# Sheet1.net
KiCad netlist of a schematic drawn in Altium Designer
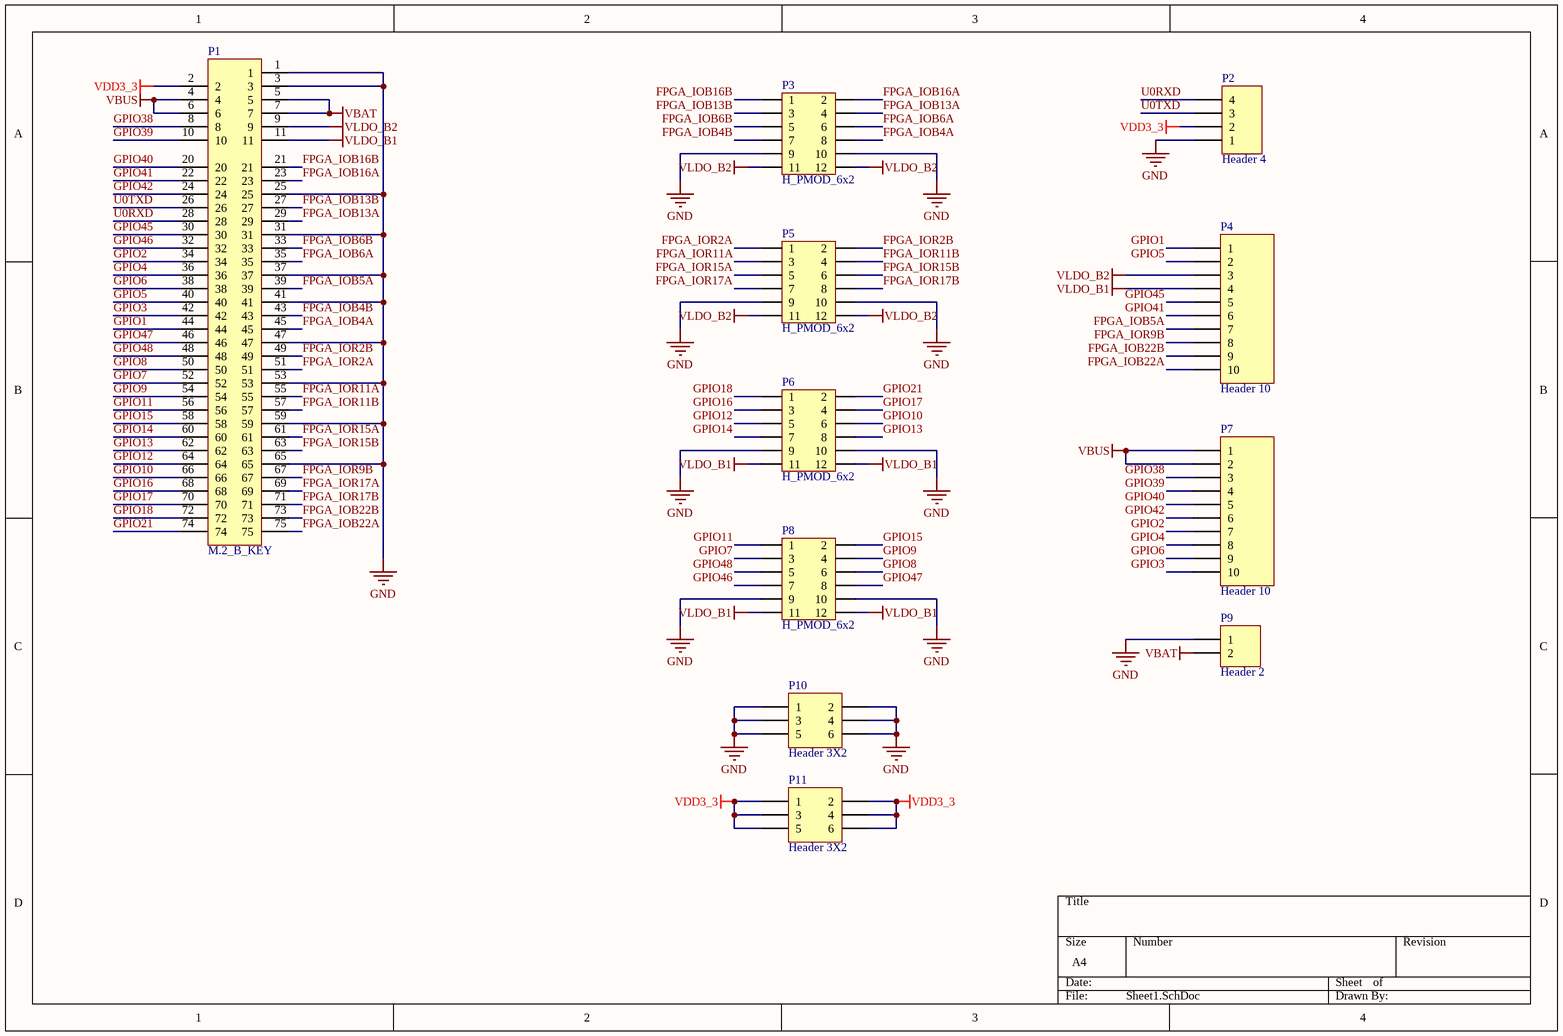
[diagram p0: Sheet1.SchDoc]

(export (version "E")
  (design (tool "Eeschema 10.0.6"))
  (components
    (comp (ref "P1")
      (value "M.2_B_KEY")
      (footprint "M.2 B KEY M")
      (libsource (lib "Micky") (part "M.2_B_KEY"))
    )
    (comp (ref "P2")
      (value "Header 4")
      (footprint "H-Header_4P-1.0mm")
      (libsource (lib "SCH_Lib") (part "H_Header_4"))
    )
    (comp (ref "P3")
      (value "H_PMOD_6x2")
      (footprint "PMOD 6x2")
      (libsource (lib "Micky") (part "H_PMOD_6x2"))
    )
    (comp (ref "P4")
      (value "Header 10")
      (footprint "10P_HDR")
      (libsource (lib "SCH_Lib") (part "H_Header_10"))
    )
    (comp (ref "P5")
      (value "H_PMOD_6x2")
      (footprint "PMOD 6x2")
      (libsource (lib "Micky") (part "H_PMOD_6x2"))
    )
    (comp (ref "P6")
      (value "H_PMOD_6x2")
      (footprint "PMOD 6x2")
      (libsource (lib "Micky") (part "H_PMOD_6x2"))
    )
    (comp (ref "P7")
      (value "Header 10")
      (footprint "10P_HDR")
      (libsource (lib "SCH_Lib") (part "H_Header_10"))
    )
    (comp (ref "P8")
      (value "H_PMOD_6x2")
      (footprint "PMOD 6x2")
      (libsource (lib "Micky") (part "H_PMOD_6x2"))
    )
    (comp (ref "P9") (value "Header 2") (footprint "BAT电池盒") (libsource (lib "SCH_Lib") (part "H_Header_2")))
    (comp (ref "P10")
      (value "Header 3X2")
      (footprint "HDR_3x2")
      (libsource (lib "SCH_Lib") (part "H_Header_3X2"))
    )
    (comp (ref "P11")
      (value "Header 3X2")
      (footprint "HDR_3x2")
      (libsource (lib "SCH_Lib") (part "H_Header_3X2"))
    )
  )
  (nets
    (net (code "1") (name "/FPGA_IOB4A") (class "Default")
      (node (ref "P1") (pin "45") (pinfunction "45_45") (pintype "passive"))
      (node (ref "P3") (pin "8") (pinfunction "8_8") (pintype "passive"))
    )
    (net (code "2") (name "/FPGA_IOB4B") (class "Default")
      (node (ref "P1") (pin "43") (pinfunction "43_43") (pintype "passive"))
      (node (ref "P3") (pin "7") (pinfunction "7_7") (pintype "passive"))
    )
    (net (code "3") (name "/FPGA_IOB5A") (class "Default")
      (node (ref "P1") (pin "39") (pinfunction "39_39") (pintype "passive"))
      (node (ref "P4") (pin "7") (pinfunction "7_7") (pintype "passive"))
    )
    (net (code "4") (name "/FPGA_IOB6A") (class "Default")
      (node (ref "P1") (pin "35") (pinfunction "35_35") (pintype "passive"))
      (node (ref "P3") (pin "6") (pinfunction "6_6") (pintype "passive"))
    )
    (net (code "5") (name "/FPGA_IOB6B") (class "Default")
      (node (ref "P1") (pin "33") (pinfunction "33_33") (pintype "passive"))
      (node (ref "P3") (pin "5") (pinfunction "5_5") (pintype "passive"))
    )
    (net (code "6") (name "/FPGA_IOB13A") (class "Default")
      (node (ref "P1") (pin "29") (pinfunction "29_29") (pintype "passive"))
      (node (ref "P3") (pin "4") (pinfunction "4_4") (pintype "passive"))
    )
    (net (code "7") (name "/FPGA_IOB13B") (class "Default")
      (node (ref "P1") (pin "27") (pinfunction "27_27") (pintype "passive"))
      (node (ref "P3") (pin "3") (pinfunction "3_3") (pintype "passive"))
    )
    (net (code "8") (name "/FPGA_IOB16A") (class "Default")
      (node (ref "P1") (pin "23") (pinfunction "23_23") (pintype "passive"))
      (node (ref "P3") (pin "2") (pinfunction "2_2") (pintype "passive"))
    )
    (net (code "9") (name "/FPGA_IOB16B") (class "Default")
      (node (ref "P1") (pin "21") (pinfunction "21_21") (pintype "passive"))
      (node (ref "P3") (pin "1") (pinfunction "1_1") (pintype "passive"))
    )
    (net (code "10") (name "/FPGA_IOB22A") (class "Default")
      (node (ref "P1") (pin "75") (pinfunction "75_75") (pintype "passive"))
      (node (ref "P4") (pin "10") (pinfunction "10_10") (pintype "passive"))
    )
    (net (code "11") (name "/FPGA_IOB22B") (class "Default")
      (node (ref "P1") (pin "73") (pinfunction "73_73") (pintype "passive"))
      (node (ref "P4") (pin "9") (pinfunction "9_9") (pintype "passive"))
    )
    (net (code "12") (name "/FPGA_IOR2A") (class "Default")
      (node (ref "P1") (pin "51") (pinfunction "51_51") (pintype "passive"))
      (node (ref "P5") (pin "1") (pinfunction "1_1") (pintype "passive"))
    )
    (net (code "13") (name "/FPGA_IOR2B") (class "Default")
      (node (ref "P1") (pin "49") (pinfunction "49_49") (pintype "passive"))
      (node (ref "P5") (pin "2") (pinfunction "2_2") (pintype "passive"))
    )
    (net (code "14") (name "/FPGA_IOR9B") (class "Default")
      (node (ref "P1") (pin "67") (pinfunction "67_67") (pintype "passive"))
      (node (ref "P4") (pin "8") (pinfunction "8_8") (pintype "passive"))
    )
    (net (code "15") (name "/FPGA_IOR11A") (class "Default")
      (node (ref "P1") (pin "55") (pinfunction "55_55") (pintype "passive"))
      (node (ref "P5") (pin "3") (pinfunction "3_3") (pintype "passive"))
    )
    (net (code "16") (name "/FPGA_IOR11B") (class "Default")
      (node (ref "P1") (pin "57") (pinfunction "57_57") (pintype "passive"))
      (node (ref "P5") (pin "4") (pinfunction "4_4") (pintype "passive"))
    )
    (net (code "17") (name "/FPGA_IOR15A") (class "Default")
      (node (ref "P1") (pin "61") (pinfunction "61_61") (pintype "passive"))
      (node (ref "P5") (pin "5") (pinfunction "5_5") (pintype "passive"))
    )
    (net (code "18") (name "/FPGA_IOR15B") (class "Default")
      (node (ref "P1") (pin "63") (pinfunction "63_63") (pintype "passive"))
      (node (ref "P5") (pin "6") (pinfunction "6_6") (pintype "passive"))
    )
    (net (code "19") (name "/FPGA_IOR17A") (class "Default")
      (node (ref "P1") (pin "69") (pinfunction "69_69") (pintype "passive"))
      (node (ref "P5") (pin "7") (pinfunction "7_7") (pintype "passive"))
    )
    (net (code "20") (name "/FPGA_IOR17B") (class "Default")
      (node (ref "P1") (pin "71") (pinfunction "71_71") (pintype "passive"))
      (node (ref "P5") (pin "8") (pinfunction "8_8") (pintype "passive"))
    )
    (net (code "21") (name "/GPIO1") (class "Default")
      (node (ref "P1") (pin "44") (pinfunction "44_44") (pintype "passive"))
      (node (ref "P4") (pin "1") (pinfunction "1_1") (pintype "passive"))
    )
    (net (code "22") (name "/GPIO2") (class "Default")
      (node (ref "P1") (pin "34") (pinfunction "34_34") (pintype "passive"))
      (node (ref "P7") (pin "7") (pinfunction "7_7") (pintype "passive"))
    )
    (net (code "23") (name "/GPIO3") (class "Default")
      (node (ref "P1") (pin "42") (pinfunction "42_42") (pintype "passive"))
      (node (ref "P7") (pin "10") (pinfunction "10_10") (pintype "passive"))
    )
    (net (code "24") (name "/GPIO4") (class "Default")
      (node (ref "P1") (pin "36") (pinfunction "36_36") (pintype "passive"))
      (node (ref "P7") (pin "8") (pinfunction "8_8") (pintype "passive"))
    )
    (net (code "25") (name "/GPIO5") (class "Default")
      (node (ref "P1") (pin "40") (pinfunction "40_40") (pintype "passive"))
      (node (ref "P4") (pin "2") (pinfunction "2_2") (pintype "passive"))
    )
    (net (code "26") (name "/GPIO6") (class "Default")
      (node (ref "P1") (pin "38") (pinfunction "38_38") (pintype "passive"))
      (node (ref "P7") (pin "9") (pinfunction "9_9") (pintype "passive"))
    )
    (net (code "27") (name "/GPIO7") (class "Default")
      (node (ref "P1") (pin "52") (pinfunction "52_52") (pintype "passive"))
      (node (ref "P8") (pin "3") (pinfunction "3_3") (pintype "passive"))
    )
    (net (code "28") (name "/GPIO8") (class "Default")
      (node (ref "P1") (pin "50") (pinfunction "50_50") (pintype "passive"))
      (node (ref "P8") (pin "6") (pinfunction "6_6") (pintype "passive"))
    )
    (net (code "29") (name "/GPIO9") (class "Default")
      (node (ref "P1") (pin "54") (pinfunction "54_54") (pintype "passive"))
      (node (ref "P8") (pin "4") (pinfunction "4_4") (pintype "passive"))
    )
    (net (code "30") (name "/GPIO10") (class "Default")
      (node (ref "P1") (pin "66") (pinfunction "66_66") (pintype "passive"))
      (node (ref "P6") (pin "6") (pinfunction "6_6") (pintype "passive"))
    )
    (net (code "31") (name "/GPIO11") (class "Default")
      (node (ref "P1") (pin "56") (pinfunction "56_56") (pintype "passive"))
      (node (ref "P8") (pin "1") (pinfunction "1_1") (pintype "passive"))
    )
    (net (code "32") (name "/GPIO12") (class "Default")
      (node (ref "P1") (pin "64") (pinfunction "64_64") (pintype "passive"))
      (node (ref "P6") (pin "5") (pinfunction "5_5") (pintype "passive"))
    )
    (net (code "33") (name "/GPIO13") (class "Default")
      (node (ref "P1") (pin "62") (pinfunction "62_62") (pintype "passive"))
      (node (ref "P6") (pin "8") (pinfunction "8_8") (pintype "passive"))
    )
    (net (code "34") (name "/GPIO14") (class "Default")
      (node (ref "P1") (pin "60") (pinfunction "60_60") (pintype "passive"))
      (node (ref "P6") (pin "7") (pinfunction "7_7") (pintype "passive"))
    )
    (net (code "35") (name "/GPIO15") (class "Default")
      (node (ref "P1") (pin "58") (pinfunction "58_58") (pintype "passive"))
      (node (ref "P8") (pin "2") (pinfunction "2_2") (pintype "passive"))
    )
    (net (code "36") (name "/GPIO16") (class "Default")
      (node (ref "P1") (pin "68") (pinfunction "68_68") (pintype "passive"))
      (node (ref "P6") (pin "3") (pinfunction "3_3") (pintype "passive"))
    )
    (net (code "37") (name "/GPIO17") (class "Default")
      (node (ref "P1") (pin "70") (pinfunction "70_70") (pintype "passive"))
      (node (ref "P6") (pin "4") (pinfunction "4_4") (pintype "passive"))
    )
    (net (code "38") (name "/GPIO18") (class "Default")
      (node (ref "P1") (pin "72") (pinfunction "72_72") (pintype "passive"))
      (node (ref "P6") (pin "1") (pinfunction "1_1") (pintype "passive"))
    )
    (net (code "39") (name "/GPIO21") (class "Default")
      (node (ref "P1") (pin "74") (pinfunction "74_74") (pintype "passive"))
      (node (ref "P6") (pin "2") (pinfunction "2_2") (pintype "passive"))
    )
    (net (code "40") (name "/GPIO38") (class "Default")
      (node (ref "P1") (pin "8") (pinfunction "8_8") (pintype "passive"))
      (node (ref "P7") (pin "3") (pinfunction "3_3") (pintype "passive"))
    )
    (net (code "41") (name "/GPIO39") (class "Default")
      (node (ref "P1") (pin "10") (pinfunction "10_10") (pintype "passive"))
      (node (ref "P7") (pin "4") (pinfunction "4_4") (pintype "passive"))
    )
    (net (code "42") (name "/GPIO40") (class "Default")
      (node (ref "P1") (pin "20") (pinfunction "20_20") (pintype "passive"))
      (node (ref "P7") (pin "5") (pinfunction "5_5") (pintype "passive"))
    )
    (net (code "43") (name "/GPIO41") (class "Default")
      (node (ref "P1") (pin "22") (pinfunction "22_22") (pintype "passive"))
      (node (ref "P4") (pin "6") (pinfunction "6_6") (pintype "passive"))
    )
    (net (code "44") (name "/GPIO42") (class "Default")
      (node (ref "P1") (pin "24") (pinfunction "24_24") (pintype "passive"))
      (node (ref "P7") (pin "6") (pinfunction "6_6") (pintype "passive"))
    )
    (net (code "45") (name "/GPIO45") (class "Default")
      (node (ref "P1") (pin "30") (pinfunction "30_30") (pintype "passive"))
      (node (ref "P4") (pin "5") (pinfunction "5_5") (pintype "passive"))
    )
    (net (code "46") (name "/GPIO46") (class "Default")
      (node (ref "P1") (pin "32") (pinfunction "32_32") (pintype "passive"))
      (node (ref "P8") (pin "7") (pinfunction "7_7") (pintype "passive"))
    )
    (net (code "47") (name "/GPIO47") (class "Default")
      (node (ref "P1") (pin "46") (pinfunction "46_46") (pintype "passive"))
      (node (ref "P8") (pin "8") (pinfunction "8_8") (pintype "passive"))
    )
    (net (code "48") (name "/GPIO48") (class "Default")
      (node (ref "P1") (pin "48") (pinfunction "48_48") (pintype "passive"))
      (node (ref "P8") (pin "5") (pinfunction "5_5") (pintype "passive"))
    )
    (net (code "49") (name "/U0RXD") (class "Default")
      (node (ref "P1") (pin "28") (pinfunction "28_28") (pintype "passive"))
      (node (ref "P2") (pin "4") (pinfunction "4_4") (pintype "passive"))
    )
    (net (code "50") (name "/U0TXD") (class "Default")
      (node (ref "P1") (pin "26") (pinfunction "26_26") (pintype "passive"))
      (node (ref "P2") (pin "3") (pinfunction "3_3") (pintype "passive"))
    )
    (net (code "51") (name "GND") (class "Default")
      (node (ref "P1") (pin "1") (pinfunction "1_1") (pintype "passive"))
      (node (ref "P1") (pin "25") (pinfunction "25_25") (pintype "passive"))
      (node (ref "P1") (pin "3") (pinfunction "3_3") (pintype "passive"))
      (node (ref "P1") (pin "31") (pinfunction "31_31") (pintype "passive"))
      (node (ref "P1") (pin "37") (pinfunction "37_37") (pintype "passive"))
      (node (ref "P1") (pin "41") (pinfunction "41_41") (pintype "passive"))
      (node (ref "P1") (pin "47") (pinfunction "47_47") (pintype "passive"))
      (node (ref "P1") (pin "53") (pinfunction "53_53") (pintype "passive"))
      (node (ref "P1") (pin "59") (pinfunction "59_59") (pintype "passive"))
      (node (ref "P1") (pin "65") (pinfunction "65_65") (pintype "passive"))
      (node (ref "P10") (pin "1") (pinfunction "1_1") (pintype "passive"))
      (node (ref "P10") (pin "2") (pinfunction "2_2") (pintype "passive"))
      (node (ref "P10") (pin "3") (pinfunction "3_3") (pintype "passive"))
      (node (ref "P10") (pin "4") (pinfunction "4_4") (pintype "passive"))
      (node (ref "P10") (pin "5") (pinfunction "5_5") (pintype "passive"))
      (node (ref "P10") (pin "6") (pinfunction "6_6") (pintype "passive"))
      (node (ref "P2") (pin "1") (pinfunction "1_1") (pintype "passive"))
      (node (ref "P3") (pin "10") (pinfunction "10_10") (pintype "passive"))
      (node (ref "P3") (pin "9") (pinfunction "9_9") (pintype "passive"))
      (node (ref "P5") (pin "10") (pinfunction "10_10") (pintype "passive"))
      (node (ref "P5") (pin "9") (pinfunction "9_9") (pintype "passive"))
      (node (ref "P6") (pin "10") (pinfunction "10_10") (pintype "passive"))
      (node (ref "P6") (pin "9") (pinfunction "9_9") (pintype "passive"))
      (node (ref "P8") (pin "10") (pinfunction "10_10") (pintype "passive"))
      (node (ref "P8") (pin "9") (pinfunction "9_9") (pintype "passive"))
      (node (ref "P9") (pin "1") (pinfunction "1_1") (pintype "passive"))
    )
    (net (code "52") (name "VBAT") (class "Default")
      (node (ref "P1") (pin "5") (pinfunction "5_5") (pintype "passive"))
      (node (ref "P1") (pin "7") (pinfunction "7_7") (pintype "passive"))
      (node (ref "P9") (pin "2") (pinfunction "2_2") (pintype "passive"))
    )
    (net (code "53") (name "VBUS") (class "Default")
      (node (ref "P1") (pin "4") (pinfunction "4_4") (pintype "passive"))
      (node (ref "P1") (pin "6") (pinfunction "6_6") (pintype "passive"))
      (node (ref "P7") (pin "1") (pinfunction "1_1") (pintype "passive"))
      (node (ref "P7") (pin "2") (pinfunction "2_2") (pintype "passive"))
    )
    (net (code "54") (name "VDD3_3") (class "Default")
      (node (ref "P1") (pin "2") (pinfunction "2_2") (pintype "passive"))
      (node (ref "P11") (pin "1") (pinfunction "1_1") (pintype "passive"))
      (node (ref "P11") (pin "2") (pinfunction "2_2") (pintype "passive"))
      (node (ref "P11") (pin "3") (pinfunction "3_3") (pintype "passive"))
      (node (ref "P11") (pin "4") (pinfunction "4_4") (pintype "passive"))
      (node (ref "P11") (pin "5") (pinfunction "5_5") (pintype "passive"))
      (node (ref "P11") (pin "6") (pinfunction "6_6") (pintype "passive"))
      (node (ref "P2") (pin "2") (pinfunction "2_2") (pintype "passive"))
    )
    (net (code "55") (name "VLDO_B1") (class "Default")
      (node (ref "P1") (pin "11") (pinfunction "11_11") (pintype "passive"))
      (node (ref "P4") (pin "4") (pinfunction "4_4") (pintype "passive"))
      (node (ref "P6") (pin "11") (pinfunction "11_11") (pintype "passive"))
      (node (ref "P6") (pin "12") (pinfunction "12_12") (pintype "passive"))
      (node (ref "P8") (pin "11") (pinfunction "11_11") (pintype "passive"))
      (node (ref "P8") (pin "12") (pinfunction "12_12") (pintype "passive"))
    )
    (net (code "56") (name "VLDO_B2") (class "Default")
      (node (ref "P1") (pin "9") (pinfunction "9_9") (pintype "passive"))
      (node (ref "P3") (pin "11") (pinfunction "11_11") (pintype "passive"))
      (node (ref "P3") (pin "12") (pinfunction "12_12") (pintype "passive"))
      (node (ref "P4") (pin "3") (pinfunction "3_3") (pintype "passive"))
      (node (ref "P5") (pin "11") (pinfunction "11_11") (pintype "passive"))
      (node (ref "P5") (pin "12") (pinfunction "12_12") (pintype "passive"))
    )
  )
)
